# 03_io_mcu.net
KiCad netlist of a schematic drawn in Altium Designer
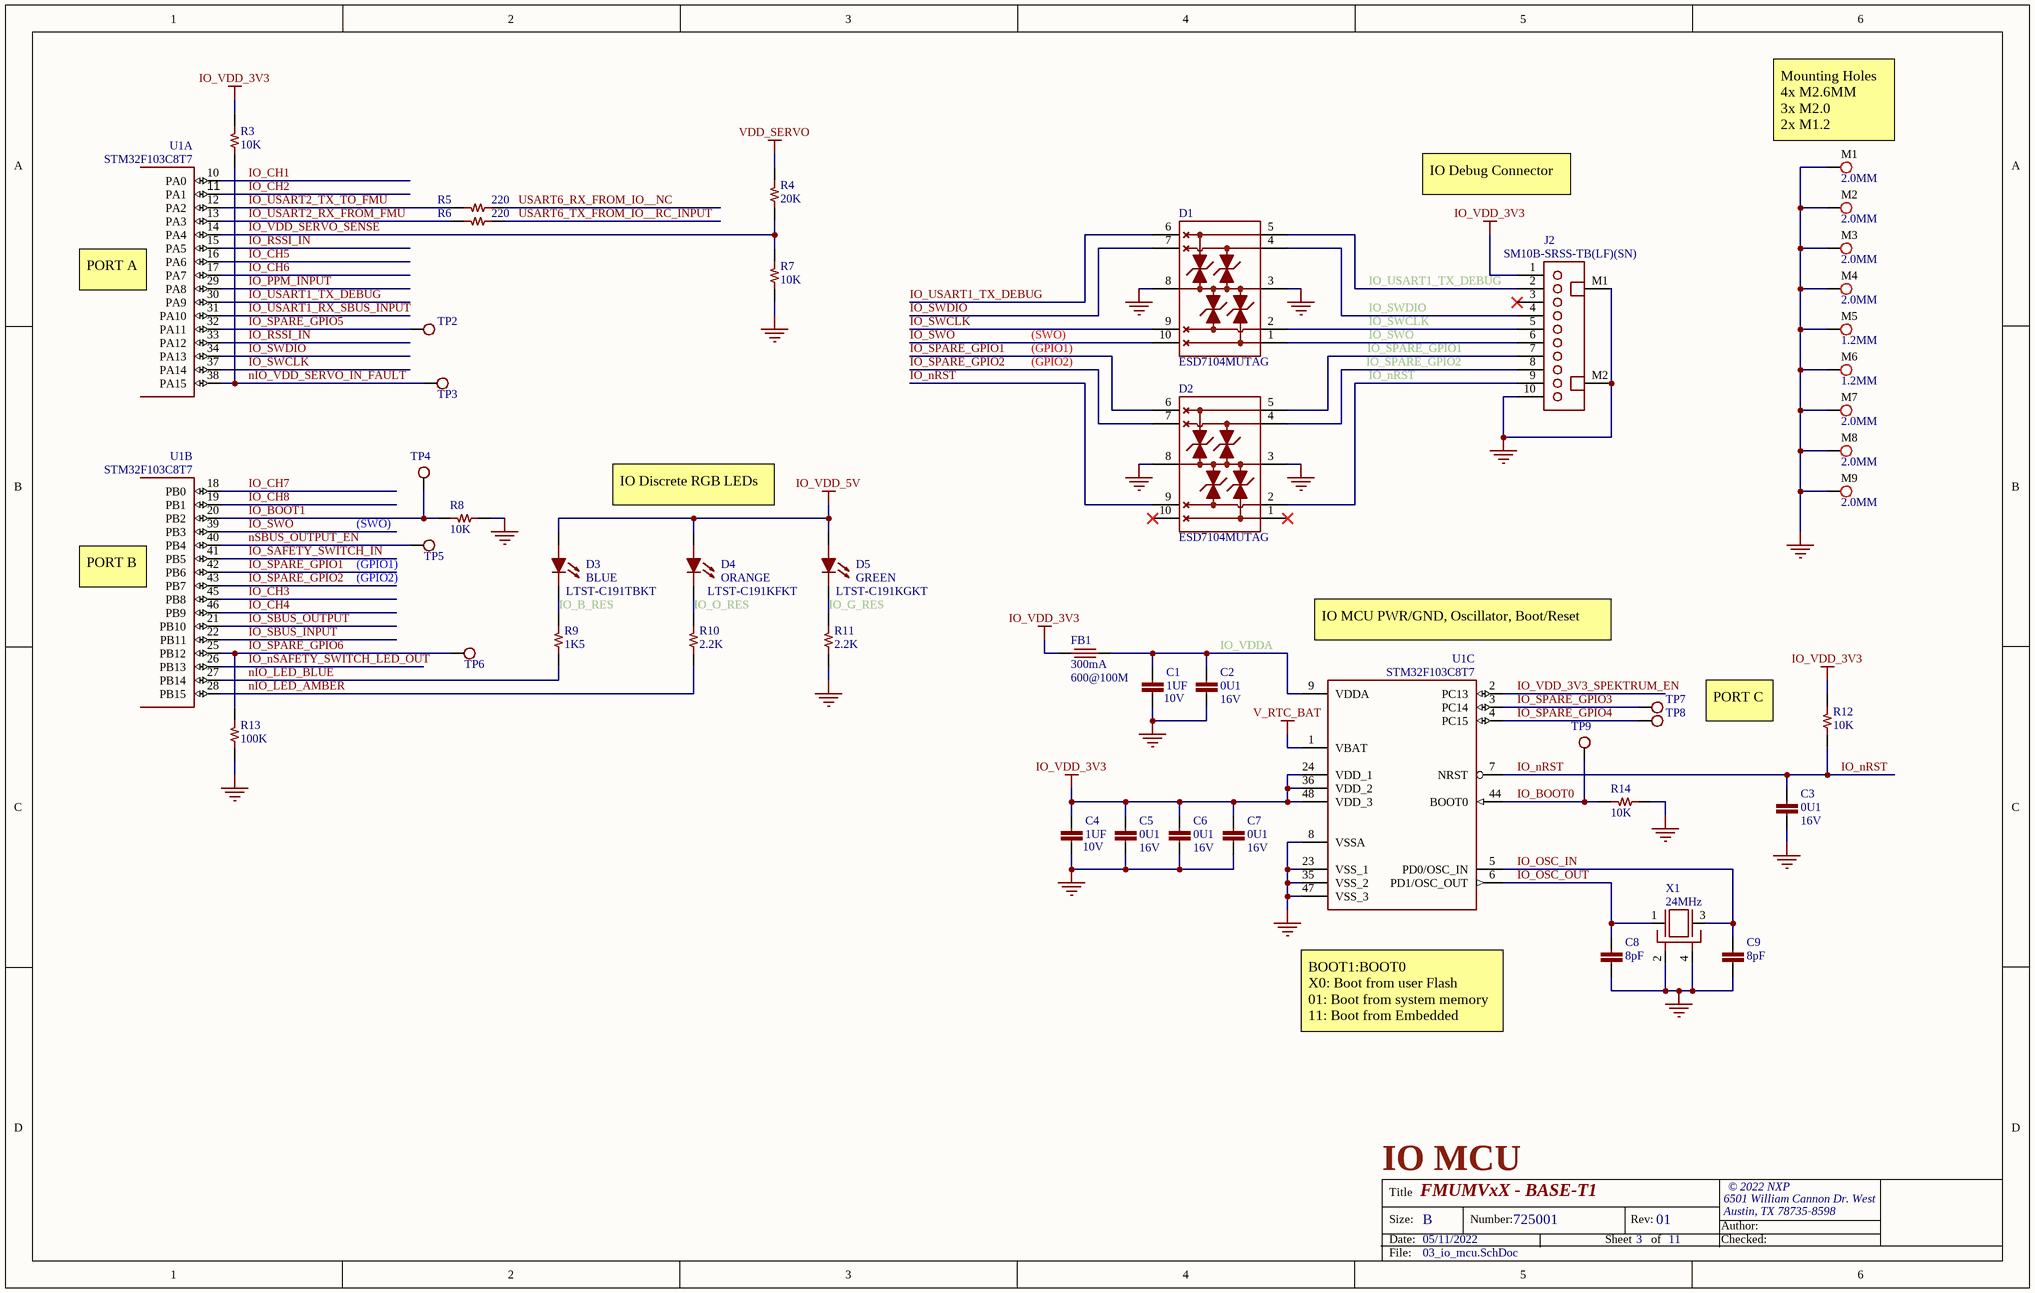
[diagram p0: 03_io_mcu.SchDoc]

(export (version "E")
  (design (tool "Eeschema 10.0.6"))
  (components
    (comp (ref "C1")
      (value "1UF")
      (footprint "CAPC100X50X56L25N")
      (description "CAP CER 1UF 20% 10V X5R 0402")
      (fields
        (field (name "MANUFACTURER") "Yageo")
        (field (name "MANUFACTURER PART NUMBER") "CC0402MRX5R6BB105")
        (field (name "VOLTAGE - RATED") "10V")
      )
      (libsource (lib "NscDG_Integrated_Library") (part "CAP_1UF_20%_10V_X5R_0402"))
    )
    (comp (ref "C2")
      (value "0U1")
      (footprint "CAPC100X50X56L25N")
      (description "CAP CER 0.1UF 10% 16V X7R 0402")
      (fields
        (field (name "TOLERANCE") "±10%")
        (field (name "MANUFACTURER") "Murata Electronics")
        (field (name "VOLTAGE - RATED") "16V")
      )
      (libsource (lib "NscDG_Integrated_Library") (part "CAP_0U1_16V_X7R_0402"))
    )
    (comp (ref "C3")
      (value "0U1")
      (footprint "CAPC100X50X56L25N")
      (description "CAP CER 0.1UF 10% 16V X7R 0402")
      (fields
        (field (name "TOLERANCE") "±10%")
        (field (name "MANUFACTURER") "Murata Electronics")
        (field (name "VOLTAGE - RATED") "16V")
      )
      (libsource (lib "NscDG_Integrated_Library") (part "CAP_0U1_16V_X7R_0402"))
    )
    (comp (ref "C4")
      (value "1UF")
      (footprint "CAPC100X50X56L25N")
      (description "CAP CER 1UF 20% 10V X5R 0402")
      (fields
        (field (name "MANUFACTURER") "Yageo")
        (field (name "MANUFACTURER PART NUMBER") "CC0402MRX5R6BB105")
        (field (name "VOLTAGE - RATED") "10V")
      )
      (libsource (lib "NscDG_Integrated_Library") (part "CAP_1UF_20%_10V_X5R_0402"))
    )
    (comp (ref "C5")
      (value "0U1")
      (footprint "CAPC100X50X56L25N")
      (description "CAP CER 0.1UF 10% 16V X7R 0402")
      (fields
        (field (name "TOLERANCE") "±10%")
        (field (name "MANUFACTURER") "Murata Electronics")
        (field (name "VOLTAGE - RATED") "16V")
      )
      (libsource (lib "NscDG_Integrated_Library") (part "CAP_0U1_16V_X7R_0402"))
    )
    (comp (ref "C6")
      (value "0U1")
      (footprint "CAPC100X50X56L25N")
      (description "CAP CER 0.1UF 10% 16V X7R 0402")
      (fields
        (field (name "TOLERANCE") "±10%")
        (field (name "MANUFACTURER") "Murata Electronics")
        (field (name "VOLTAGE - RATED") "16V")
      )
      (libsource (lib "NscDG_Integrated_Library") (part "CAP_0U1_16V_X7R_0402"))
    )
    (comp (ref "C7")
      (value "0U1")
      (footprint "CAPC100X50X56L25N")
      (description "CAP CER 0.1UF 10% 16V X7R 0402")
      (fields
        (field (name "TOLERANCE") "±10%")
        (field (name "MANUFACTURER") "Murata Electronics")
        (field (name "VOLTAGE - RATED") "16V")
      )
      (libsource (lib "NscDG_Integrated_Library") (part "CAP_0U1_16V_X7R_0402"))
    )
    (comp (ref "C8")
      (value "8pF")
      (footprint "CAPC100X50X56L25N")
      (description "CAP CER 8PF 50V C0G/NP0 0402")
      (fields
        (field (name "MANUFACTURER") "Yageo")
        (field (name "MANUFACTURER PART NUMBER") "CC0402DRNPO9BN8R0")
      )
      (libsource (lib "NscDG_Integrated_Library") (part "CAP_8PF_50V_NPO_0402"))
    )
    (comp (ref "C9")
      (value "8pF")
      (footprint "CAPC100X50X56L25N")
      (description "CAP CER 8PF 50V C0G/NP0 0402")
      (fields
        (field (name "MANUFACTURER") "Yageo")
        (field (name "MANUFACTURER PART NUMBER") "CC0402DRNPO9BN8R0")
      )
      (libsource (lib "NscDG_Integrated_Library") (part "CAP_8PF_50V_NPO_0402"))
    )
    (comp (ref "D1")
      (value "DIODE TVS BIDIRECTIONAL 5V 10V 10UDFN")
      (footprint "UDFN10P50_250X100X55L35X20N")
      (fields
        (field (name "MANUFACTURER") "ON Semiconductor")
        (field (name "MANUFACTURER PART NUMBER") "ESD7104MUTAG")
      )
      (libsource (lib "NscDG_Integrated_Library") (part "DIODE_TVS_4X_10UDFN"))
    )
    (comp (ref "D2")
      (value "DIODE TVS BIDIRECTIONAL 5V 10V 10UDFN")
      (footprint "UDFN10P50_250X100X55L35X20N")
      (fields
        (field (name "MANUFACTURER") "ON Semiconductor")
        (field (name "MANUFACTURER PART NUMBER") "ESD7104MUTAG")
      )
      (libsource (lib "NscDG_Integrated_Library") (part "DIODE_TVS_4X_10UDFN"))
    )
    (comp (ref "D3")
      (value "LED BLUE CLEAR 0603 SMD")
      (footprint "LEDSC80X160X65L40N_BLU")
      (fields
        (field (name "MANUFACTURER") "Lite-On Inc.")
        (field (name "COLOR") "BLUE")
        (field (name "MANUFACTURER PART NUMBER") "LTST-C191TBKT")
      )
      (libsource (lib "NscDG_Integrated_Library") (part "DIODE_LED_BLUE_0603"))
    )
    (comp (ref "D4")
      (value "LED ORANGE CLEAR 0603 SMD")
      (footprint "LEDSC80X160X65L40N_ORA")
      (fields
        (field (name "MANUFACTURER") "Lite-On Inc.")
        (field (name "COLOR") "ORANGE")
        (field (name "MANUFACTURER PART NUMBER") "LTST-C191KFKT")
      )
      (libsource (lib "NscDG_Integrated_Library") (part "DIODE_LED_ORANGE_0603"))
    )
    (comp (ref "D5")
      (value "LED GREEN CLEAR 0603 SMD")
      (footprint "LEDSC80X160X65L40N_GRN")
      (fields
        (field (name "MANUFACTURER") "Lite-On Inc.")
        (field (name "COLOR") "GREEN")
        (field (name "MANUFACTURER PART NUMBER") "LTST-C191KGKT")
      )
      (libsource (lib "NscDG_Integrated_Library") (part "DIODE_LED_GREEN_0603"))
    )
    (comp (ref "FB1")
      (value "600@100M")
      (footprint "BEADC100X50X55L25")
      (description "IND FERRITE 600@100M 300mA 0402")
      (fields
        (field (name "MANUFACTURER") "Murata Electronics North America")
        (field (name "MANUFACTURER PART NUMBER") "BLM15HG601SN1D")
        (field (name "CURRENT") "300mA")
      )
      (libsource (lib "NscDG_Integrated_Library") (part "IND_FERRITE_600@100M_300mA_0402"))
    )
    (comp (ref "J2")
      (value "CONN HEADER SH 10POS SIDE 1MM SMT")
      (footprint "JST_SM10B-SRSS-TB")
      (fields
        (field (name "MANUFACTURER") "JST Sales America Inc.")
        (field (name "MANUFACTURER PART NUMBER") "SM10B-SRSS-TB(LF)(SN)")
      )
      (libsource (lib "NscDG_Integrated_Library") (part "CONN_JST_SH_10PIN_RA_SMT"))
    )
    (comp (ref "M1")
      (value "MOUNT HOLE 2MM 3.6MM 8VIAS TH")
      (footprint "MOUNT_HOLE_2MM_3.6MM_8via_TH")
      (fields (field (name "ID") "2.0MM"))
      (libsource (lib "NscDG_Integrated_Library") (part "MOUNT_HOLE_2MM_3.6MM_8VIAS_TH"))
    )
    (comp (ref "M2")
      (value "MOUNT HOLE 2MM 3.6MM 8VIAS TH")
      (footprint "MOUNT_HOLE_2MM_3.6MM_8via_TH")
      (fields (field (name "ID") "2.0MM"))
      (libsource (lib "NscDG_Integrated_Library") (part "MOUNT_HOLE_2MM_3.6MM_8VIAS_TH"))
    )
    (comp (ref "M3")
      (value "MOUNT HOLE 2MM 3.6MM 8VIAS TH")
      (footprint "MOUNT_HOLE_2MM_3.6MM_8via_TH")
      (fields (field (name "ID") "2.0MM"))
      (libsource (lib "NscDG_Integrated_Library") (part "MOUNT_HOLE_2MM_3.6MM_8VIAS_TH"))
    )
    (comp (ref "M4")
      (value "MOUNT HOLE 2MM 3.6MM 8VIAS TH")
      (footprint "MOUNT_HOLE_2MM_3.6MM_8via_TH")
      (fields (field (name "ID") "2.0MM"))
      (libsource (lib "NscDG_Integrated_Library") (part "MOUNT_HOLE_2MM_3.6MM_8VIAS_TH"))
    )
    (comp (ref "M5")
      (value "MOUNT HOLE 1.2MM TH")
      (footprint "MOUNT_HOLE_1.2MM_TH")
      (fields (field (name "ID") "1.2MM"))
      (libsource (lib "NscDG_Integrated_Library") (part "MOUNT_HOLE_1.2MM_TH"))
    )
    (comp (ref "M6")
      (value "MOUNT HOLE 1.2MM TH")
      (footprint "MOUNT_HOLE_1.2MM_TH")
      (fields (field (name "ID") "1.2MM"))
      (libsource (lib "NscDG_Integrated_Library") (part "MOUNT_HOLE_1.2MM_TH"))
    )
    (comp (ref "M7")
      (value "MOUNT HOLE 2MM 3.6MM 8VIAS TH")
      (footprint "MOUNT_HOLE_2MM_3.6MM_8via_TH")
      (fields (field (name "ID") "2.0MM"))
      (libsource (lib "NscDG_Integrated_Library") (part "MOUNT_HOLE_2MM_3.6MM_8VIAS_TH"))
    )
    (comp (ref "M8")
      (value "MOUNT HOLE 2MM 3.6MM 8VIAS TH")
      (footprint "MOUNT_HOLE_2MM_3.6MM_8via_TH")
      (fields (field (name "ID") "2.0MM"))
      (libsource (lib "NscDG_Integrated_Library") (part "MOUNT_HOLE_2MM_3.6MM_8VIAS_TH"))
    )
    (comp (ref "M9")
      (value "MOUNT HOLE 2MM 3.6MM 8VIAS TH")
      (footprint "MOUNT_HOLE_2MM_3.6MM_8via_TH")
      (fields (field (name "ID") "2.0MM"))
      (libsource (lib "NscDG_Integrated_Library") (part "MOUNT_HOLE_2MM_3.6MM_8VIAS_TH"))
    )
    (comp (ref "R3")
      (value "10K")
      (footprint "RESC100X50X40L25")
      (description "RES SMD 10K OHM 1% 1/16W 0402")
      (fields (field (name "TOLERANCE") "±1%") (field (name "MANUFACTURER") "Vishay Dale"))
      (libsource (lib "NscDG_Integrated_Library") (part "RES_10K_1%_1/16W_0402"))
    )
    (comp (ref "R4")
      (value "20K")
      (footprint "RESC100X50X40L25")
      (description "RES SMD 20K OHM 1% 1/16W 0402")
      (fields (field (name "TOLERANCE") "±1%") (field (name "MANUFACTURER") "Yageo"))
      (libsource (lib "NscDG_Integrated_Library") (part "RES_20K_1%_1/16W_0402"))
    )
    (comp (ref "R5")
      (value "220")
      (footprint "RESC100X50X40L25")
      (description "RES SMD 220 OHM 1% 1/16W 0402")
      (fields (field (name "TOLERANCE") "±1%") (field (name "POWER") "1/16W"))
      (libsource (lib "NscDG_Integrated_Library") (part "RES_220_1%_1/16W_0402"))
    )
    (comp (ref "R6")
      (value "220")
      (footprint "RESC100X50X40L25")
      (description "RES SMD 220 OHM 1% 1/16W 0402")
      (fields (field (name "TOLERANCE") "±1%") (field (name "POWER") "1/16W"))
      (libsource (lib "NscDG_Integrated_Library") (part "RES_220_1%_1/16W_0402"))
    )
    (comp (ref "R7")
      (value "10K")
      (footprint "RESC100X50X40L25")
      (description "RES SMD 10K OHM 1% 1/16W 0402")
      (fields (field (name "TOLERANCE") "±1%") (field (name "MANUFACTURER") "Vishay Dale"))
      (libsource (lib "NscDG_Integrated_Library") (part "RES_10K_1%_1/16W_0402"))
    )
    (comp (ref "R8")
      (value "10K")
      (footprint "RESC100X50X40L25")
      (description "RES SMD 10K OHM 1% 1/16W 0402")
      (fields (field (name "TOLERANCE") "±1%") (field (name "MANUFACTURER") "Vishay Dale"))
      (libsource (lib "NscDG_Integrated_Library") (part "RES_10K_1%_1/16W_0402"))
    )
    (comp (ref "R9")
      (value "1K5")
      (footprint "RESC100X50X40L25")
      (description "RES SMD 1.5K OHM 1% 1/16W 0402")
      (fields (field (name "TOLERANCE") "±1%") (field (name "MANUFACTURER") "Yageo"))
      (libsource (lib "NscDG_Integrated_Library") (part "RES_1K5_1%_1/16W_0402"))
    )
    (comp (ref "R10")
      (value "2.2K")
      (footprint "RESC100X50X40L25")
      (description "RES SMD 2.2K OHM 1% 1/16W 0402")
      (fields (field (name "TOLERANCE") "±1%") (field (name "MANUFACTURER") "Yageo"))
      (libsource (lib "NscDG_Integrated_Library") (part "RES_2K2_1%_1/16W_0402"))
    )
    (comp (ref "R11")
      (value "2.2K")
      (footprint "RESC100X50X40L25")
      (description "RES SMD 2.2K OHM 1% 1/16W 0402")
      (fields (field (name "TOLERANCE") "±1%") (field (name "MANUFACTURER") "Yageo"))
      (libsource (lib "NscDG_Integrated_Library") (part "RES_2K2_1%_1/16W_0402"))
    )
    (comp (ref "R12")
      (value "10K")
      (footprint "RESC100X50X40L25")
      (description "RES SMD 10K OHM 1% 1/16W 0402")
      (fields (field (name "TOLERANCE") "±1%") (field (name "MANUFACTURER") "Vishay Dale"))
      (libsource (lib "NscDG_Integrated_Library") (part "RES_10K_1%_1/16W_0402"))
    )
    (comp (ref "R13")
      (value "100K")
      (footprint "RESC100X50X40L25")
      (description "RES SMD 100K OHM 1% 1/16W 0402")
      (fields (field (name "TOLERANCE") "±1%") (field (name "MANUFACTURER") "Yageo"))
      (libsource (lib "NscDG_Integrated_Library") (part "RES_100K_1%_1/16W_0402"))
    )
    (comp (ref "R14")
      (value "10K")
      (footprint "RESC100X50X40L25")
      (description "RES SMD 10K OHM 1% 1/16W 0402")
      (fields (field (name "TOLERANCE") "±1%") (field (name "MANUFACTURER") "Vishay Dale"))
      (libsource (lib "NscDG_Integrated_Library") (part "RES_10K_1%_1/16W_0402"))
    )
    (comp (ref "TP2")
      (value "TESTPOINT PAD SMD")
      (footprint "TEST_PAD_1MM")
      (libsource (lib "NscDG_Integrated_Library") (part "TESTPOINT_PAD_SMD"))
    )
    (comp (ref "TP3")
      (value "TESTPOINT PAD SMD")
      (footprint "TEST_PAD_1MM")
      (libsource (lib "NscDG_Integrated_Library") (part "TESTPOINT_PAD_SMD"))
    )
    (comp (ref "TP4")
      (value "TESTPOINT PAD SMD")
      (footprint "TEST_PAD_1MM")
      (libsource (lib "NscDG_Integrated_Library") (part "TESTPOINT_PAD_SMD"))
    )
    (comp (ref "TP5")
      (value "TESTPOINT PAD SMD")
      (footprint "TEST_PAD_1MM")
      (libsource (lib "NscDG_Integrated_Library") (part "TESTPOINT_PAD_SMD"))
    )
    (comp (ref "TP6")
      (value "TESTPOINT PAD SMD")
      (footprint "TEST_PAD_1MM")
      (libsource (lib "NscDG_Integrated_Library") (part "TESTPOINT_PAD_SMD"))
    )
    (comp (ref "TP7")
      (value "TESTPOINT PAD SMD")
      (footprint "TEST_PAD_1MM")
      (libsource (lib "NscDG_Integrated_Library") (part "TESTPOINT_PAD_SMD"))
    )
    (comp (ref "TP8")
      (value "TESTPOINT PAD SMD")
      (footprint "TEST_PAD_1MM")
      (libsource (lib "NscDG_Integrated_Library") (part "TESTPOINT_PAD_SMD"))
    )
    (comp (ref "TP9")
      (value "TESTPOINT PAD SMD")
      (footprint "TEST_PAD_1MM")
      (libsource (lib "NscDG_Integrated_Library") (part "TESTPOINT_PAD_SMD"))
    )
    (comp (ref "U1")
      (value "IC MCU 32BIT 64KB FLASH 48LQFP")
      (footprint "QFP48P50_900X900X160L60X22N")
      (fields
        (field (name "MANUFACTURER") "STMicroelectronics")
        (field (name "MANUFACTURER PART NUMBER") "STM32F103C8T7")
      )
      (libsource (lib "NscDG_Integrated_Library") (part "IC_STM32F103C8T7"))
    )
    (comp (ref "X1")
      (value "CRYSTAL 24.0000MHZ 8PF SMD")
      (footprint "XTAL_4PIN_320X250X80")
      (fields
        (field (name "MANUFACTURER") "Kyocera International Inc. Electronic Components")
        (field (name "MANUFACTURER PART NUMBER") "CX3225SB24000D0FLJCC")
        (field (name "FREQUENCY") "24MHz")
      )
      (libsource (lib "NscDG_Integrated_Library") (part "XTAL_24MHZ_4-SMD"))
    )
  )
  (nets
    (net (code "1") (name "/IO_BOOT0") (class "Default")
      (node (ref "R14") (pin "1") (pinfunction "1_1") (pintype "passive"))
      (node (ref "TP9") (pin "1") (pinfunction "1_1") (pintype "passive"))
      (node (ref "U1") (pin "44") (pinfunction "BOOT0_44") (pintype "input"))
    )
    (net (code "2") (name "/IO_BOOT1") (class "Default")
      (node (ref "R8") (pin "1") (pinfunction "1_1") (pintype "passive"))
      (node (ref "TP4") (pin "1") (pinfunction "1_1") (pintype "passive"))
      (node (ref "U1") (pin "20") (pinfunction "PB2_20") (pintype "bidirectional"))
    )
    (net (code "3") (name "/IO_B_RES") (class "Default")
      (node (ref "D3") (pin "C") (pinfunction "C_C") (pintype "passive"))
      (node (ref "R9") (pin "1") (pinfunction "1_1") (pintype "passive"))
    )
    (net (code "4") (name "/IO_CH1") (class "Default")
      (node (ref "U1") (pin "10") (pinfunction "PA0_10") (pintype "bidirectional"))
    )
    (net (code "5") (name "/IO_CH2") (class "Default")
      (node (ref "U1") (pin "11") (pinfunction "PA1_11") (pintype "bidirectional"))
    )
    (net (code "6") (name "/IO_CH3") (class "Default")
      (node (ref "U1") (pin "45") (pinfunction "PB8_45") (pintype "bidirectional"))
    )
    (net (code "7") (name "/IO_CH4") (class "Default")
      (node (ref "U1") (pin "46") (pinfunction "PB9_46") (pintype "bidirectional"))
    )
    (net (code "8") (name "/IO_CH5") (class "Default")
      (node (ref "U1") (pin "16") (pinfunction "PA6_16") (pintype "bidirectional"))
    )
    (net (code "9") (name "/IO_CH6") (class "Default")
      (node (ref "U1") (pin "17") (pinfunction "PA7_17") (pintype "bidirectional"))
    )
    (net (code "10") (name "/IO_CH7") (class "Default")
      (node (ref "U1") (pin "18") (pinfunction "PB0_18") (pintype "bidirectional"))
    )
    (net (code "11") (name "/IO_CH8") (class "Default")
      (node (ref "U1") (pin "19") (pinfunction "PB1_19") (pintype "bidirectional"))
    )
    (net (code "12") (name "/IO_G_RES") (class "Default")
      (node (ref "D5") (pin "C") (pinfunction "C_C") (pintype "passive"))
      (node (ref "R11") (pin "1") (pinfunction "1_1") (pintype "passive"))
    )
    (net (code "13") (name "/IO_OSC_IN") (class "Default")
      (node (ref "C9") (pin "1") (pinfunction "1_1") (pintype "passive"))
      (node (ref "U1") (pin "5") (pinfunction "PD0/OSC_IN_5") (pintype "passive"))
      (node (ref "X1") (pin "3") (pinfunction "3_3") (pintype "passive"))
    )
    (net (code "14") (name "/IO_OSC_OUT") (class "Default")
      (node (ref "C8") (pin "1") (pinfunction "1_1") (pintype "passive"))
      (node (ref "U1") (pin "6") (pinfunction "PD1/OSC_OUT_6") (pintype "output"))
      (node (ref "X1") (pin "1") (pinfunction "1_1") (pintype "passive"))
    )
    (net (code "15") (name "/IO_O_RES") (class "Default")
      (node (ref "D4") (pin "C") (pinfunction "C_C") (pintype "passive"))
      (node (ref "R10") (pin "1") (pinfunction "1_1") (pintype "passive"))
    )
    (net (code "16") (name "/IO_PPM_INPUT") (class "Default")
      (node (ref "U1") (pin "29") (pinfunction "PA8_29") (pintype "bidirectional"))
    )
    (net (code "17") (name "/IO_RSSI_IN") (class "Default")
      (node (ref "U1") (pin "15") (pinfunction "PA5_15") (pintype "bidirectional"))
      (node (ref "U1") (pin "33") (pinfunction "PA12_33") (pintype "bidirectional"))
    )
    (net (code "18") (name "/IO_SAFETY_SWITCH_IN") (class "Default")
      (node (ref "U1") (pin "41") (pinfunction "PB5_41") (pintype "bidirectional"))
    )
    (net (code "19") (name "/IO_SBUS_INPUT") (class "Default")
      (node (ref "U1") (pin "22") (pinfunction "PB11_22") (pintype "bidirectional"))
    )
    (net (code "20") (name "/IO_SBUS_OUTPUT") (class "Default")
      (node (ref "U1") (pin "21") (pinfunction "PB10_21") (pintype "bidirectional"))
    )
    (net (code "21") (name "/IO_SPARE_GPIO1") (class "Default")
      (node (ref "D2") (pin "5") (pinfunction "5_5") (pintype "passive"))
      (node (ref "D2") (pin "6") (pinfunction "NC_6") (pintype "passive"))
      (node (ref "J2") (pin "7") (pinfunction "7_7") (pintype "passive"))
      (node (ref "U1") (pin "42") (pinfunction "PB6_42") (pintype "bidirectional"))
    )
    (net (code "22") (name "/IO_SPARE_GPIO2") (class "Default")
      (node (ref "D2") (pin "4") (pinfunction "4_4") (pintype "passive"))
      (node (ref "D2") (pin "7") (pinfunction "NC_7") (pintype "passive"))
      (node (ref "J2") (pin "8") (pinfunction "8_8") (pintype "passive"))
      (node (ref "U1") (pin "43") (pinfunction "PB7_43") (pintype "bidirectional"))
    )
    (net (code "23") (name "/IO_SPARE_GPIO3") (class "Default")
      (node (ref "TP7") (pin "1") (pinfunction "1_1") (pintype "passive"))
      (node (ref "U1") (pin "3") (pinfunction "PC14_3") (pintype "bidirectional"))
    )
    (net (code "24") (name "/IO_SPARE_GPIO4") (class "Default")
      (node (ref "TP8") (pin "1") (pinfunction "1_1") (pintype "passive"))
      (node (ref "U1") (pin "4") (pinfunction "PC15_4") (pintype "bidirectional"))
    )
    (net (code "25") (name "/IO_SPARE_GPIO5") (class "Default")
      (node (ref "TP2") (pin "1") (pinfunction "1_1") (pintype "passive"))
      (node (ref "U1") (pin "32") (pinfunction "PA11_32") (pintype "bidirectional"))
    )
    (net (code "26") (name "/IO_SPARE_GPIO6") (class "Default")
      (node (ref "R13") (pin "1") (pinfunction "1_1") (pintype "passive"))
      (node (ref "TP6") (pin "1") (pinfunction "1_1") (pintype "passive"))
      (node (ref "U1") (pin "25") (pinfunction "PB12_25") (pintype "bidirectional"))
    )
    (net (code "27") (name "/IO_SWCLK") (class "Default")
      (node (ref "D1") (pin "2") (pinfunction "2_2") (pintype "passive"))
      (node (ref "D1") (pin "9") (pinfunction "NC_9") (pintype "passive"))
      (node (ref "J2") (pin "5") (pinfunction "5_5") (pintype "passive"))
      (node (ref "U1") (pin "37") (pinfunction "PA14_37") (pintype "bidirectional"))
    )
    (net (code "28") (name "/IO_SWDIO") (class "Default")
      (node (ref "D1") (pin "4") (pinfunction "4_4") (pintype "passive"))
      (node (ref "D1") (pin "7") (pinfunction "NC_7") (pintype "passive"))
      (node (ref "J2") (pin "4") (pinfunction "4_4") (pintype "passive"))
      (node (ref "U1") (pin "34") (pinfunction "PA13_34") (pintype "bidirectional"))
    )
    (net (code "29") (name "/IO_SWO") (class "Default")
      (node (ref "D1") (pin "1") (pinfunction "1_1") (pintype "passive"))
      (node (ref "D1") (pin "10") (pinfunction "NC_10") (pintype "passive"))
      (node (ref "J2") (pin "6") (pinfunction "6_6") (pintype "passive"))
      (node (ref "U1") (pin "39") (pinfunction "PB3_39") (pintype "bidirectional"))
    )
    (net (code "30") (name "/IO_USART1_RX_SBUS_INPUT") (class "Default")
      (node (ref "U1") (pin "31") (pinfunction "PA10_31") (pintype "bidirectional"))
    )
    (net (code "31") (name "/IO_USART1_TX_DEBUG") (class "Default")
      (node (ref "D1") (pin "5") (pinfunction "5_5") (pintype "passive"))
      (node (ref "D1") (pin "6") (pinfunction "NC_6") (pintype "passive"))
      (node (ref "J2") (pin "2") (pinfunction "2_2") (pintype "passive"))
      (node (ref "U1") (pin "30") (pinfunction "PA9_30") (pintype "bidirectional"))
    )
    (net (code "32") (name "/IO_USART2_RX_FROM_FMU") (class "Default")
      (node (ref "R6") (pin "1") (pinfunction "1_1") (pintype "passive"))
      (node (ref "U1") (pin "13") (pinfunction "PA3_13") (pintype "bidirectional"))
    )
    (net (code "33") (name "/IO_USART2_TX_TO_FMU") (class "Default")
      (node (ref "R5") (pin "1") (pinfunction "1_1") (pintype "passive"))
      (node (ref "U1") (pin "12") (pinfunction "PA2_12") (pintype "bidirectional"))
    )
    (net (code "34") (name "/IO_VDDA") (class "Default")
      (node (ref "C1") (pin "1") (pinfunction "1_1") (pintype "passive"))
      (node (ref "C2") (pin "1") (pinfunction "1_1") (pintype "passive"))
      (node (ref "FB1") (pin "2") (pinfunction "2_2") (pintype "passive"))
      (node (ref "U1") (pin "9") (pinfunction "VDDA_9") (pintype "power_in"))
    )
    (net (code "35") (name "/IO_VDD_3V3_SPEKTRUM_EN") (class "Default")
      (node (ref "U1") (pin "2") (pinfunction "PC13_2") (pintype "bidirectional"))
    )
    (net (code "36") (name "/IO_VDD_SERVO_SENSE") (class "Default")
      (node (ref "R4") (pin "2") (pinfunction "2_2") (pintype "passive"))
      (node (ref "R7") (pin "1") (pinfunction "1_1") (pintype "passive"))
      (node (ref "U1") (pin "14") (pinfunction "PA4_14") (pintype "bidirectional"))
    )
    (net (code "37") (name "/IO_nRST") (class "Default")
      (node (ref "C3") (pin "1") (pinfunction "1_1") (pintype "passive"))
      (node (ref "D2") (pin "2") (pinfunction "2_2") (pintype "passive"))
      (node (ref "D2") (pin "9") (pinfunction "NC_9") (pintype "passive"))
      (node (ref "J2") (pin "9") (pinfunction "9_9") (pintype "passive"))
      (node (ref "R12") (pin "2") (pinfunction "2_2") (pintype "passive"))
      (node (ref "U1") (pin "7") (pinfunction "NRST_7") (pintype "passive"))
    )
    (net (code "38") (name "/IO_nSAFETY_SWITCH_LED_OUT") (class "Default")
      (node (ref "U1") (pin "26") (pinfunction "PB13_26") (pintype "bidirectional"))
    )
    (net (code "39") (name "/USART6_RX_FROM_IO__NC") (class "Default")
      (node (ref "R5") (pin "2") (pinfunction "2_2") (pintype "passive"))
    )
    (net (code "40") (name "/USART6_TX_FROM_IO__RC_INPUT") (class "Default")
      (node (ref "R6") (pin "2") (pinfunction "2_2") (pintype "passive"))
    )
    (net (code "41") (name "/nIO_LED_AMBER") (class "Default")
      (node (ref "R10") (pin "2") (pinfunction "2_2") (pintype "passive"))
      (node (ref "U1") (pin "28") (pinfunction "PB15_28") (pintype "bidirectional"))
    )
    (net (code "42") (name "/nIO_LED_BLUE") (class "Default")
      (node (ref "R9") (pin "2") (pinfunction "2_2") (pintype "passive"))
      (node (ref "U1") (pin "27") (pinfunction "PB14_27") (pintype "bidirectional"))
    )
    (net (code "43") (name "/nIO_VDD_SERVO_IN_FAULT") (class "Default")
      (node (ref "R3") (pin "2") (pinfunction "2_2") (pintype "passive"))
      (node (ref "TP3") (pin "1") (pinfunction "1_1") (pintype "passive"))
      (node (ref "U1") (pin "38") (pinfunction "PA15_38") (pintype "bidirectional"))
    )
    (net (code "44") (name "/nSBUS_OUTPUT_EN") (class "Default")
      (node (ref "TP5") (pin "1") (pinfunction "1_1") (pintype "passive"))
      (node (ref "U1") (pin "40") (pinfunction "PB4_40") (pintype "bidirectional"))
    )
    (net (code "45") (name "GND") (class "Default")
      (node (ref "C1") (pin "2") (pinfunction "2_2") (pintype "passive"))
      (node (ref "C2") (pin "2") (pinfunction "2_2") (pintype "passive"))
      (node (ref "C3") (pin "2") (pinfunction "2_2") (pintype "passive"))
      (node (ref "C4") (pin "2") (pinfunction "2_2") (pintype "passive"))
      (node (ref "C5") (pin "2") (pinfunction "2_2") (pintype "passive"))
      (node (ref "C6") (pin "2") (pinfunction "2_2") (pintype "passive"))
      (node (ref "C7") (pin "2") (pinfunction "2_2") (pintype "passive"))
      (node (ref "C8") (pin "2") (pinfunction "2_2") (pintype "passive"))
      (node (ref "C9") (pin "2") (pinfunction "2_2") (pintype "passive"))
      (node (ref "D1") (pin "3") (pinfunction "GND_3") (pintype "passive"))
      (node (ref "D1") (pin "8") (pinfunction "GND_8") (pintype "passive"))
      (node (ref "D2") (pin "3") (pinfunction "GND_3") (pintype "passive"))
      (node (ref "D2") (pin "8") (pinfunction "GND_8") (pintype "passive"))
      (node (ref "J2") (pin "10") (pinfunction "10_10") (pintype "passive"))
      (node (ref "J2") (pin "M1") (pinfunction "M1_M1") (pintype "passive"))
      (node (ref "J2") (pin "M2") (pinfunction "M2_M2") (pintype "passive"))
      (node (ref "M1") (pin "1") (pinfunction "1_1") (pintype "passive"))
      (node (ref "M2") (pin "1") (pinfunction "1_1") (pintype "passive"))
      (node (ref "M3") (pin "1") (pinfunction "1_1") (pintype "passive"))
      (node (ref "M4") (pin "1") (pinfunction "1_1") (pintype "passive"))
      (node (ref "M5") (pin "1") (pinfunction "1_1") (pintype "passive"))
      (node (ref "M6") (pin "1") (pinfunction "1_1") (pintype "passive"))
      (node (ref "M7") (pin "1") (pinfunction "1_1") (pintype "passive"))
      (node (ref "M8") (pin "1") (pinfunction "1_1") (pintype "passive"))
      (node (ref "M9") (pin "1") (pinfunction "1_1") (pintype "passive"))
      (node (ref "R11") (pin "2") (pinfunction "2_2") (pintype "passive"))
      (node (ref "R13") (pin "2") (pinfunction "2_2") (pintype "passive"))
      (node (ref "R14") (pin "2") (pinfunction "2_2") (pintype "passive"))
      (node (ref "R7") (pin "2") (pinfunction "2_2") (pintype "passive"))
      (node (ref "R8") (pin "2") (pinfunction "2_2") (pintype "passive"))
      (node (ref "U1") (pin "23") (pinfunction "VSS_1_23") (pintype "passive"))
      (node (ref "U1") (pin "35") (pinfunction "VSS_2_35") (pintype "passive"))
      (node (ref "U1") (pin "47") (pinfunction "VSS_3_47") (pintype "passive"))
      (node (ref "U1") (pin "8") (pinfunction "VSSA_8") (pintype "passive"))
      (node (ref "X1") (pin "2") (pinfunction "2_2") (pintype "passive"))
      (node (ref "X1") (pin "4") (pinfunction "4_4") (pintype "passive"))
    )
    (net (code "46") (name "IO_VDD_3V3") (class "Default")
      (node (ref "C4") (pin "1") (pinfunction "1_1") (pintype "passive"))
      (node (ref "C5") (pin "1") (pinfunction "1_1") (pintype "passive"))
      (node (ref "C6") (pin "1") (pinfunction "1_1") (pintype "passive"))
      (node (ref "C7") (pin "1") (pinfunction "1_1") (pintype "passive"))
      (node (ref "FB1") (pin "1") (pinfunction "1_1") (pintype "passive"))
      (node (ref "J2") (pin "1") (pinfunction "1_1") (pintype "passive"))
      (node (ref "R12") (pin "1") (pinfunction "1_1") (pintype "passive"))
      (node (ref "R3") (pin "1") (pinfunction "1_1") (pintype "passive"))
      (node (ref "U1") (pin "24") (pinfunction "VDD_1_24") (pintype "power_in"))
      (node (ref "U1") (pin "36") (pinfunction "VDD_2_36") (pintype "power_in"))
      (node (ref "U1") (pin "48") (pinfunction "VDD_3_48") (pintype "power_in"))
    )
    (net (code "47") (name "IO_VDD_5V") (class "Default")
      (node (ref "D3") (pin "A") (pinfunction "A_A") (pintype "passive"))
      (node (ref "D4") (pin "A") (pinfunction "A_A") (pintype "passive"))
      (node (ref "D5") (pin "A") (pinfunction "A_A") (pintype "passive"))
    )
    (net (code "48") (name "VDD_SERVO") (class "Default")
      (node (ref "R4") (pin "1") (pinfunction "1_1") (pintype "passive"))
    )
    (net (code "49") (name "V_RTC_BAT") (class "Default")
      (node (ref "U1") (pin "1") (pinfunction "VBAT_1") (pintype "power_in"))
    )
    (net (code "50") (name "unconnected-(D2-NC-Pad10)") (class "Default")
      (node (ref "D2") (pin "10") (pinfunction "NC_10") (pintype "passive+no_connect"))
    )
    (net (code "51") (name "unconnected-(D2-Pad1)") (class "Default")
      (node (ref "D2") (pin "1") (pinfunction "1_1") (pintype "passive+no_connect"))
    )
    (net (code "52") (name "unconnected-(J2-Pad3)") (class "Default")
      (node (ref "J2") (pin "3") (pinfunction "3_3") (pintype "passive+no_connect"))
    )
  )
)
